# IP_show.net
KiCad netlist of a schematic drawn in EAGLE
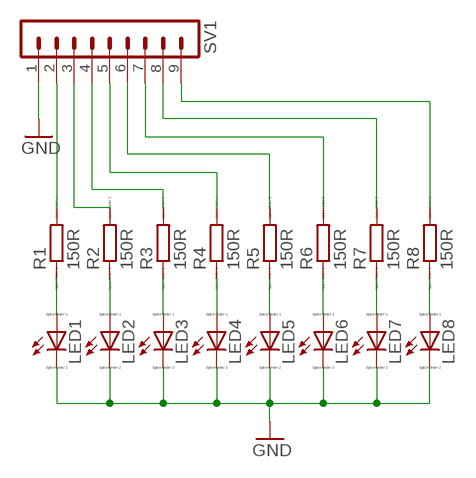
[diagram p0: schematic, sheet 1]

(export (version "E")
  (design (tool "Eeschema 10.0.6"))
  (components
    (comp (ref "LED1")
      (value "LED_E")
      (footprint "eagle-import:LED_1206")
      (libsource (lib "eagle-import") (part "LED_E"))
    )
    (comp (ref "LED2")
      (value "LED_E")
      (footprint "eagle-import:LED_1206")
      (libsource (lib "eagle-import") (part "LED_E"))
    )
    (comp (ref "LED3")
      (value "LED_E")
      (footprint "eagle-import:LED_1206")
      (libsource (lib "eagle-import") (part "LED_E"))
    )
    (comp (ref "LED4")
      (value "LED_E")
      (footprint "eagle-import:LED_1206")
      (libsource (lib "eagle-import") (part "LED_E"))
    )
    (comp (ref "LED5")
      (value "LED_E")
      (footprint "eagle-import:LED_1206")
      (libsource (lib "eagle-import") (part "LED_E"))
    )
    (comp (ref "LED6")
      (value "LED_E")
      (footprint "eagle-import:LED_1206")
      (libsource (lib "eagle-import") (part "LED_E"))
    )
    (comp (ref "LED7")
      (value "LED_E")
      (footprint "eagle-import:LED_1206")
      (libsource (lib "eagle-import") (part "LED_E"))
    )
    (comp (ref "LED8")
      (value "LED_E")
      (footprint "eagle-import:LED_1206")
      (libsource (lib "eagle-import") (part "LED_E"))
    )
    (comp (ref "R1")
      (value "150R")
      (footprint "eagle-import:R1206")
      (libsource (lib "eagle-import") (part "RR1206"))
    )
    (comp (ref "R2")
      (value "150R")
      (footprint "eagle-import:R1206")
      (libsource (lib "eagle-import") (part "RR1206"))
    )
    (comp (ref "R3")
      (value "150R")
      (footprint "eagle-import:R1206")
      (libsource (lib "eagle-import") (part "RR1206"))
    )
    (comp (ref "R4")
      (value "150R")
      (footprint "eagle-import:R1206")
      (libsource (lib "eagle-import") (part "RR1206"))
    )
    (comp (ref "R5")
      (value "150R")
      (footprint "eagle-import:R1206")
      (libsource (lib "eagle-import") (part "RR1206"))
    )
    (comp (ref "R6")
      (value "150R")
      (footprint "eagle-import:R1206")
      (libsource (lib "eagle-import") (part "RR1206"))
    )
    (comp (ref "R7")
      (value "150R")
      (footprint "eagle-import:R1206")
      (libsource (lib "eagle-import") (part "RR1206"))
    )
    (comp (ref "R8")
      (value "150R")
      (footprint "eagle-import:R1206")
      (libsource (lib "eagle-import") (part "RR1206"))
    )
    (comp (ref "SV1")
      (value "MA09-1")
      (footprint "eagle-import:MA09-1")
      (libsource (lib "eagle-import") (part "MA09-1"))
    )
  )
  (nets
    (net (code "1") (name "GND") (class "Default")
      (node (ref "LED1") (pin "C") (pinfunction "C_C") (pintype "passive"))
      (node (ref "LED2") (pin "C") (pinfunction "C_C") (pintype "passive"))
      (node (ref "LED3") (pin "C") (pinfunction "C_C") (pintype "passive"))
      (node (ref "LED4") (pin "C") (pinfunction "C_C") (pintype "passive"))
      (node (ref "LED5") (pin "C") (pinfunction "C_C") (pintype "passive"))
      (node (ref "LED6") (pin "C") (pinfunction "C_C") (pintype "passive"))
      (node (ref "LED7") (pin "C") (pinfunction "C_C") (pintype "passive"))
      (node (ref "LED8") (pin "C") (pinfunction "C_C") (pintype "passive"))
      (node (ref "SV1") (pin "1") (pinfunction "1_1") (pintype "passive"))
    )
    (net (code "2") (name "Net-(LED1-PadA)") (class "Default")
      (node (ref "LED1") (pin "A") (pinfunction "A_A") (pintype "passive"))
      (node (ref "R1") (pin "1") (pinfunction "1_1") (pintype "passive"))
    )
    (net (code "3") (name "Net-(LED2-PadA)") (class "Default")
      (node (ref "LED2") (pin "A") (pinfunction "A_A") (pintype "passive"))
      (node (ref "R2") (pin "1") (pinfunction "1_1") (pintype "passive"))
    )
    (net (code "4") (name "Net-(LED3-PadA)") (class "Default")
      (node (ref "LED3") (pin "A") (pinfunction "A_A") (pintype "passive"))
      (node (ref "R3") (pin "1") (pinfunction "1_1") (pintype "passive"))
    )
    (net (code "5") (name "Net-(LED4-PadA)") (class "Default")
      (node (ref "LED4") (pin "A") (pinfunction "A_A") (pintype "passive"))
      (node (ref "R4") (pin "1") (pinfunction "1_1") (pintype "passive"))
    )
    (net (code "6") (name "Net-(LED5-PadA)") (class "Default")
      (node (ref "LED5") (pin "A") (pinfunction "A_A") (pintype "passive"))
      (node (ref "R5") (pin "1") (pinfunction "1_1") (pintype "passive"))
    )
    (net (code "7") (name "Net-(LED6-PadA)") (class "Default")
      (node (ref "LED6") (pin "A") (pinfunction "A_A") (pintype "passive"))
      (node (ref "R6") (pin "1") (pinfunction "1_1") (pintype "passive"))
    )
    (net (code "8") (name "Net-(LED7-PadA)") (class "Default")
      (node (ref "LED7") (pin "A") (pinfunction "A_A") (pintype "passive"))
      (node (ref "R7") (pin "1") (pinfunction "1_1") (pintype "passive"))
    )
    (net (code "9") (name "Net-(LED8-PadA)") (class "Default")
      (node (ref "LED8") (pin "A") (pinfunction "A_A") (pintype "passive"))
      (node (ref "R8") (pin "1") (pinfunction "1_1") (pintype "passive"))
    )
    (net (code "10") (name "Net-(R1-Pad2)") (class "Default")
      (node (ref "R1") (pin "2") (pinfunction "2_2") (pintype "passive"))
      (node (ref "SV1") (pin "2") (pinfunction "2_2") (pintype "passive"))
    )
    (net (code "11") (name "Net-(R2-Pad2)") (class "Default")
      (node (ref "R2") (pin "2") (pinfunction "2_2") (pintype "passive"))
      (node (ref "SV1") (pin "3") (pinfunction "3_3") (pintype "passive"))
    )
    (net (code "12") (name "Net-(R3-Pad2)") (class "Default")
      (node (ref "R3") (pin "2") (pinfunction "2_2") (pintype "passive"))
      (node (ref "SV1") (pin "4") (pinfunction "4_4") (pintype "passive"))
    )
    (net (code "13") (name "Net-(R4-Pad2)") (class "Default")
      (node (ref "R4") (pin "2") (pinfunction "2_2") (pintype "passive"))
      (node (ref "SV1") (pin "5") (pinfunction "5_5") (pintype "passive"))
    )
    (net (code "14") (name "Net-(R5-Pad2)") (class "Default")
      (node (ref "R5") (pin "2") (pinfunction "2_2") (pintype "passive"))
      (node (ref "SV1") (pin "6") (pinfunction "6_6") (pintype "passive"))
    )
    (net (code "15") (name "Net-(R6-Pad2)") (class "Default")
      (node (ref "R6") (pin "2") (pinfunction "2_2") (pintype "passive"))
      (node (ref "SV1") (pin "7") (pinfunction "7_7") (pintype "passive"))
    )
    (net (code "16") (name "Net-(R7-Pad2)") (class "Default")
      (node (ref "R7") (pin "2") (pinfunction "2_2") (pintype "passive"))
      (node (ref "SV1") (pin "8") (pinfunction "8_8") (pintype "passive"))
    )
    (net (code "17") (name "Net-(R8-Pad2)") (class "Default")
      (node (ref "R8") (pin "2") (pinfunction "2_2") (pintype "passive"))
      (node (ref "SV1") (pin "9") (pinfunction "9_9") (pintype "passive"))
    )
  )
)
